# slider.net
KiCad netlist of a schematic drawn in EAGLE
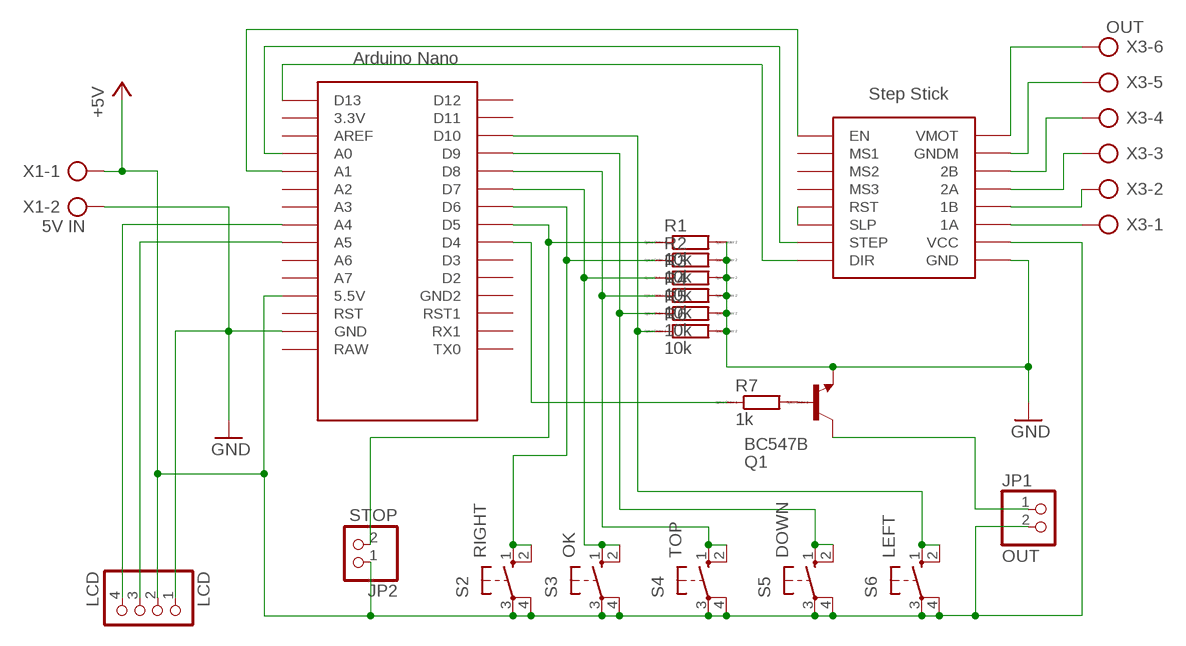
[diagram p0: schematic, sheet 1]

(export (version "E")
  (design (tool "Eeschema 10.0.6"))
  (components
    (comp (ref "JP1")
      (value "OUT")
      (footprint "eagle-import:1X02")
      (libsource (lib "eagle-import") (part "PINHD-1X2"))
    )
    (comp (ref "JP2")
      (value "STOP")
      (footprint "eagle-import:1X02")
      (libsource (lib "eagle-import") (part "PINHD-1X2"))
    )
    (comp (ref "LCD")
      (value "LCD")
      (footprint "eagle-import:1X04")
      (libsource (lib "eagle-import") (part "PINHD-1X4"))
    )
    (comp (ref "Q1")
      (value "BC547B")
      (footprint "eagle-import:TO92")
      (libsource (lib "eagle-import") (part "BC547B"))
    )
    (comp (ref "R1")
      (value "10k")
      (footprint "eagle-import:0207_10")
      (libsource (lib "eagle-import") (part "R0207/10"))
    )
    (comp (ref "R2")
      (value "10k")
      (footprint "eagle-import:0207_10")
      (libsource (lib "eagle-import") (part "R0207/10"))
    )
    (comp (ref "R3")
      (value "10k")
      (footprint "eagle-import:0207_10")
      (libsource (lib "eagle-import") (part "R0207/10"))
    )
    (comp (ref "R4")
      (value "10k")
      (footprint "eagle-import:0207_10")
      (libsource (lib "eagle-import") (part "R0207/10"))
    )
    (comp (ref "R5")
      (value "10k")
      (footprint "eagle-import:0207_10")
      (libsource (lib "eagle-import") (part "R0207/10"))
    )
    (comp (ref "R6")
      (value "10k")
      (footprint "eagle-import:0207_10")
      (libsource (lib "eagle-import") (part "R0207/10"))
    )
    (comp (ref "R7")
      (value "1k")
      (footprint "eagle-import:0207_10")
      (libsource (lib "eagle-import") (part "R0207/10"))
    )
    (comp (ref "S2")
      (value "RIGHT")
      (footprint "eagle-import:B3F-10XX")
      (fields (field (name "MPN") "B3F-1000"))
      (libsource (lib "eagle-import") (part "10-XX"))
    )
    (comp (ref "S3")
      (value "OK")
      (footprint "eagle-import:B3F-10XX")
      (fields (field (name "MPN") "B3F-1000"))
      (libsource (lib "eagle-import") (part "10-XX"))
    )
    (comp (ref "S4")
      (value "TOP")
      (footprint "eagle-import:B3F-10XX")
      (fields (field (name "MPN") "B3F-1000"))
      (libsource (lib "eagle-import") (part "10-XX"))
    )
    (comp (ref "S5")
      (value "DOWN")
      (footprint "eagle-import:B3F-10XX")
      (fields (field (name "MPN") "B3F-1000"))
      (libsource (lib "eagle-import") (part "10-XX"))
    )
    (comp (ref "S6")
      (value "LEFT")
      (footprint "eagle-import:B3F-10XX")
      (fields (field (name "MPN") "B3F-1000"))
      (libsource (lib "eagle-import") (part "10-XX"))
    )
    (comp (ref "U$1")
      (value "NANO")
      (footprint "eagle-import:NANO")
      (libsource (lib "eagle-import") (part "NANO"))
    )
    (comp (ref "U$2")
      (value "STEP-STICK")
      (footprint "eagle-import:STEP-STICK")
      (libsource (lib "eagle-import") (part "STEP-STICK"))
    )
    (comp (ref "X1")
      (value "5V IN")
      (footprint "eagle-import:AK500_2")
      (libsource (lib "eagle-import") (part "AK500/2"))
    )
    (comp (ref "X3")
      (value "OUT")
      (footprint "eagle-import:AK500_6")
      (libsource (lib "eagle-import") (part "AK500/6"))
    )
  )
  (nets
    (net (code "1") (name "+5V") (class "Default")
      (node (ref "JP1") (pin "2") (pinfunction "2_2") (pintype "passive"))
      (node (ref "JP2") (pin "1") (pinfunction "1_1") (pintype "passive"))
      (node (ref "LCD") (pin "2") (pinfunction "2_2") (pintype "passive"))
      (node (ref "S2") (pin "3") (pinfunction "P_3") (pintype "passive"))
      (node (ref "S2") (pin "4") (pinfunction "P1_4") (pintype "passive"))
      (node (ref "S3") (pin "3") (pinfunction "P_3") (pintype "passive"))
      (node (ref "S3") (pin "4") (pinfunction "P1_4") (pintype "passive"))
      (node (ref "S4") (pin "3") (pinfunction "P_3") (pintype "passive"))
      (node (ref "S4") (pin "4") (pinfunction "P1_4") (pintype "passive"))
      (node (ref "S5") (pin "3") (pinfunction "P_3") (pintype "passive"))
      (node (ref "S5") (pin "4") (pinfunction "P1_4") (pintype "passive"))
      (node (ref "S6") (pin "3") (pinfunction "P_3") (pintype "passive"))
      (node (ref "S6") (pin "4") (pinfunction "P1_4") (pintype "passive"))
      (node (ref "U$1") (pin "5V") (pinfunction "5.5V_5V") (pintype "bidirectional"))
      (node (ref "U$2") (pin "VCC") (pinfunction "VCC_VCC") (pintype "bidirectional"))
      (node (ref "X1") (pin "1") (pinfunction "KL_1") (pintype "passive"))
    )
    (net (code "2") (name "GND") (class "Default")
      (node (ref "LCD") (pin "1") (pinfunction "1_1") (pintype "passive"))
      (node (ref "Q1") (pin "1") (pinfunction "E_1") (pintype "passive"))
      (node (ref "R1") (pin "2") (pinfunction "2_2") (pintype "passive"))
      (node (ref "R2") (pin "2") (pinfunction "2_2") (pintype "passive"))
      (node (ref "R3") (pin "2") (pinfunction "2_2") (pintype "passive"))
      (node (ref "R4") (pin "2") (pinfunction "2_2") (pintype "passive"))
      (node (ref "R5") (pin "2") (pinfunction "2_2") (pintype "passive"))
      (node (ref "R6") (pin "2") (pinfunction "2_2") (pintype "passive"))
      (node (ref "U$1") (pin "GND") (pinfunction "GND_GND") (pintype "bidirectional"))
      (node (ref "U$2") (pin "GND") (pinfunction "GND_GND") (pintype "bidirectional"))
      (node (ref "X1") (pin "2") (pinfunction "KL_2") (pintype "passive"))
    )
    (net (code "3") (name "Net-(JP2-Pad2)") (class "Default")
      (node (ref "JP2") (pin "2") (pinfunction "2_2") (pintype "passive"))
      (node (ref "R1") (pin "1") (pinfunction "1_1") (pintype "passive"))
      (node (ref "U$1") (pin "D5") (pinfunction "D5_D5") (pintype "bidirectional"))
    )
    (net (code "4") (name "Net-(LCD-Pad3)") (class "Default")
      (node (ref "LCD") (pin "3") (pinfunction "3_3") (pintype "passive"))
      (node (ref "U$1") (pin "A5") (pinfunction "A5_A5") (pintype "bidirectional"))
    )
    (net (code "5") (name "Net-(LCD-Pad4)") (class "Default")
      (node (ref "LCD") (pin "4") (pinfunction "4_4") (pintype "passive"))
      (node (ref "U$1") (pin "A4") (pinfunction "A4_A4") (pintype "bidirectional"))
    )
    (net (code "6") (name "Net-(Q1-B)") (class "Default")
      (node (ref "Q1") (pin "2") (pinfunction "B_2") (pintype "passive"))
      (node (ref "R7") (pin "2") (pinfunction "2_2") (pintype "passive"))
    )
    (net (code "7") (name "Net-(Q1-C)") (class "Default")
      (node (ref "JP1") (pin "1") (pinfunction "1_1") (pintype "passive"))
      (node (ref "Q1") (pin "3") (pinfunction "C_3") (pintype "passive"))
    )
    (net (code "8") (name "Net-(R7-Pad1)") (class "Default")
      (node (ref "R7") (pin "1") (pinfunction "1_1") (pintype "passive"))
      (node (ref "U$1") (pin "D4") (pinfunction "D4_D4") (pintype "bidirectional"))
    )
    (net (code "9") (name "Net-(S2-S)") (class "Default")
      (node (ref "R2") (pin "1") (pinfunction "1_1") (pintype "passive"))
      (node (ref "S2") (pin "1") (pinfunction "S_1") (pintype "passive"))
      (node (ref "S2") (pin "2") (pinfunction "S1_2") (pintype "passive"))
      (node (ref "U$1") (pin "D6") (pinfunction "D6_D6") (pintype "bidirectional"))
    )
    (net (code "10") (name "Net-(S3-S)") (class "Default")
      (node (ref "R3") (pin "1") (pinfunction "1_1") (pintype "passive"))
      (node (ref "S3") (pin "1") (pinfunction "S_1") (pintype "passive"))
      (node (ref "S3") (pin "2") (pinfunction "S1_2") (pintype "passive"))
      (node (ref "U$1") (pin "D7") (pinfunction "D7_D7") (pintype "bidirectional"))
    )
    (net (code "11") (name "Net-(S4-S)") (class "Default")
      (node (ref "R4") (pin "1") (pinfunction "1_1") (pintype "passive"))
      (node (ref "S4") (pin "1") (pinfunction "S_1") (pintype "passive"))
      (node (ref "S4") (pin "2") (pinfunction "S1_2") (pintype "passive"))
      (node (ref "U$1") (pin "D8") (pinfunction "D8_D8") (pintype "bidirectional"))
    )
    (net (code "12") (name "Net-(S5-S)") (class "Default")
      (node (ref "R5") (pin "1") (pinfunction "1_1") (pintype "passive"))
      (node (ref "S5") (pin "1") (pinfunction "S_1") (pintype "passive"))
      (node (ref "S5") (pin "2") (pinfunction "S1_2") (pintype "passive"))
      (node (ref "U$1") (pin "D9") (pinfunction "D9_D9") (pintype "bidirectional"))
    )
    (net (code "13") (name "Net-(S6-S)") (class "Default")
      (node (ref "R6") (pin "1") (pinfunction "1_1") (pintype "passive"))
      (node (ref "S6") (pin "1") (pinfunction "S_1") (pintype "passive"))
      (node (ref "S6") (pin "2") (pinfunction "S1_2") (pintype "passive"))
      (node (ref "U$1") (pin "D10") (pinfunction "D10_D10") (pintype "bidirectional"))
    )
    (net (code "14") (name "Net-(U$1-PadA1)") (class "Default")
      (node (ref "U$1") (pin "A1") (pinfunction "A1_A1") (pintype "bidirectional"))
      (node (ref "U$2") (pin "EN") (pinfunction "EN_EN") (pintype "bidirectional"))
    )
    (net (code "15") (name "Net-(U$1-PadD13)") (class "Default")
      (node (ref "U$1") (pin "D13") (pinfunction "D13_D13") (pintype "bidirectional"))
      (node (ref "U$2") (pin "DIR") (pinfunction "DIR_DIR") (pintype "bidirectional"))
    )
    (net (code "16") (name "Net-(U$2-PadRST)") (class "Default")
      (node (ref "U$2") (pin "RST") (pinfunction "RST_RST") (pintype "bidirectional"))
      (node (ref "U$2") (pin "SLP") (pinfunction "SLP_SLP") (pintype "bidirectional"))
    )
    (net (code "17") (name "Net-(U$2-STEP)") (class "Default")
      (node (ref "U$1") (pin "A0") (pinfunction "A0_A0") (pintype "bidirectional"))
      (node (ref "U$2") (pin "SPT") (pinfunction "STEP_SPT") (pintype "bidirectional"))
    )
    (net (code "18") (name "Net-(X3A-KL)") (class "Default")
      (node (ref "U$2") (pin "1A") (pinfunction "1A_1A") (pintype "bidirectional"))
      (node (ref "X3") (pin "1") (pinfunction "KL_1") (pintype "passive"))
    )
    (net (code "19") (name "Net-(X3B-KL)") (class "Default")
      (node (ref "U$2") (pin "1B") (pinfunction "1B_1B") (pintype "bidirectional"))
      (node (ref "X3") (pin "2") (pinfunction "KL_2") (pintype "passive"))
    )
    (net (code "20") (name "Net-(X3C-KL)") (class "Default")
      (node (ref "U$2") (pin "2A") (pinfunction "2A_2A") (pintype "bidirectional"))
      (node (ref "X3") (pin "3") (pinfunction "KL_3") (pintype "passive"))
    )
    (net (code "21") (name "Net-(X3D-KL)") (class "Default")
      (node (ref "U$2") (pin "2B") (pinfunction "2B_2B") (pintype "bidirectional"))
      (node (ref "X3") (pin "4") (pinfunction "KL_4") (pintype "passive"))
    )
    (net (code "22") (name "Net-(X3E-KL)") (class "Default")
      (node (ref "U$2") (pin "GNDM") (pinfunction "GNDM_GNDM") (pintype "bidirectional"))
      (node (ref "X3") (pin "5") (pinfunction "KL_5") (pintype "passive"))
    )
    (net (code "23") (name "Net-(X3F-KL)") (class "Default")
      (node (ref "U$2") (pin "VMOT") (pinfunction "VMOT_VMOT") (pintype "bidirectional"))
      (node (ref "X3") (pin "6") (pinfunction "KL_6") (pintype "passive"))
    )
    (net (code "24") (name "unconnected-(U$1-GND2-PadGND1)") (class "Default")
      (node (ref "U$1") (pin "GND1") (pinfunction "GND2_GND1") (pintype "bidirectional"))
    )
    (net (code "25") (name "unconnected-(U$1-Pad3.3V)") (class "Default")
      (node (ref "U$1") (pin "3.3V") (pinfunction "3.3V_3.3V") (pintype "bidirectional"))
    )
    (net (code "26") (name "unconnected-(U$1-PadA2)") (class "Default")
      (node (ref "U$1") (pin "A2") (pinfunction "A2_A2") (pintype "bidirectional"))
    )
    (net (code "27") (name "unconnected-(U$1-PadA3)") (class "Default")
      (node (ref "U$1") (pin "A3") (pinfunction "A3_A3") (pintype "bidirectional"))
    )
    (net (code "28") (name "unconnected-(U$1-PadA6)") (class "Default")
      (node (ref "U$1") (pin "A6") (pinfunction "A6_A6") (pintype "bidirectional"))
    )
    (net (code "29") (name "unconnected-(U$1-PadA7)") (class "Default")
      (node (ref "U$1") (pin "A7") (pinfunction "A7_A7") (pintype "bidirectional"))
    )
    (net (code "30") (name "unconnected-(U$1-PadAREF)") (class "Default")
      (node (ref "U$1") (pin "AREF") (pinfunction "AREF_AREF") (pintype "bidirectional"))
    )
    (net (code "31") (name "unconnected-(U$1-PadD2)") (class "Default")
      (node (ref "U$1") (pin "D2") (pinfunction "D2_D2") (pintype "bidirectional"))
    )
    (net (code "32") (name "unconnected-(U$1-PadD3)") (class "Default")
      (node (ref "U$1") (pin "D3") (pinfunction "D3_D3") (pintype "bidirectional"))
    )
    (net (code "33") (name "unconnected-(U$1-PadD11)") (class "Default")
      (node (ref "U$1") (pin "D11") (pinfunction "D11_D11") (pintype "bidirectional"))
    )
    (net (code "34") (name "unconnected-(U$1-PadD12)") (class "Default")
      (node (ref "U$1") (pin "D12") (pinfunction "D12_D12") (pintype "bidirectional"))
    )
    (net (code "35") (name "unconnected-(U$1-PadICSP1)") (class "Default")
      (node (ref "U$1") (pin "ICSP1") (pinfunction "ICSP1_ICSP1") (pintype "bidirectional"))
    )
    (net (code "36") (name "unconnected-(U$1-PadICSP2)") (class "Default")
      (node (ref "U$1") (pin "ICSP2") (pinfunction "ICSP2_ICSP2") (pintype "bidirectional"))
    )
    (net (code "37") (name "unconnected-(U$1-PadICSP3)") (class "Default")
      (node (ref "U$1") (pin "ICSP3") (pinfunction "ICSP3_ICSP3") (pintype "bidirectional"))
    )
    (net (code "38") (name "unconnected-(U$1-PadICSP4)") (class "Default")
      (node (ref "U$1") (pin "ICSP4") (pinfunction "ICSP4_ICSP4") (pintype "bidirectional"))
    )
    (net (code "39") (name "unconnected-(U$1-PadICSP5)") (class "Default")
      (node (ref "U$1") (pin "ICSP5") (pinfunction "ICSP5_ICSP5") (pintype "bidirectional"))
    )
    (net (code "40") (name "unconnected-(U$1-PadICSP6)") (class "Default")
      (node (ref "U$1") (pin "ICSP6") (pinfunction "ICSP6_ICSP6") (pintype "bidirectional"))
    )
    (net (code "41") (name "unconnected-(U$1-PadRAW)") (class "Default")
      (node (ref "U$1") (pin "RAW") (pinfunction "RAW_RAW") (pintype "bidirectional"))
    )
    (net (code "42") (name "unconnected-(U$1-PadRST)") (class "Default")
      (node (ref "U$1") (pin "RST") (pinfunction "RST_RST") (pintype "bidirectional"))
    )
    (net (code "43") (name "unconnected-(U$1-PadRST1)") (class "Default")
      (node (ref "U$1") (pin "RST1") (pinfunction "RST1_RST1") (pintype "bidirectional"))
    )
    (net (code "44") (name "unconnected-(U$1-PadRX1)") (class "Default")
      (node (ref "U$1") (pin "RX1") (pinfunction "RX1_RX1") (pintype "bidirectional"))
    )
    (net (code "45") (name "unconnected-(U$1-PadTX0)") (class "Default")
      (node (ref "U$1") (pin "TX0") (pinfunction "TX0_TX0") (pintype "bidirectional"))
    )
    (net (code "46") (name "unconnected-(U$2-PadMS1)") (class "Default")
      (node (ref "U$2") (pin "MS1") (pinfunction "MS1_MS1") (pintype "bidirectional"))
    )
    (net (code "47") (name "unconnected-(U$2-PadMS2)") (class "Default")
      (node (ref "U$2") (pin "MS2") (pinfunction "MS2_MS2") (pintype "bidirectional"))
    )
    (net (code "48") (name "unconnected-(U$2-PadMS3)") (class "Default")
      (node (ref "U$2") (pin "MS3") (pinfunction "MS3_MS3") (pintype "bidirectional"))
    )
  )
)
